# Board_Schamatic07.net
KiCad netlist of a schematic drawn in EAGLE
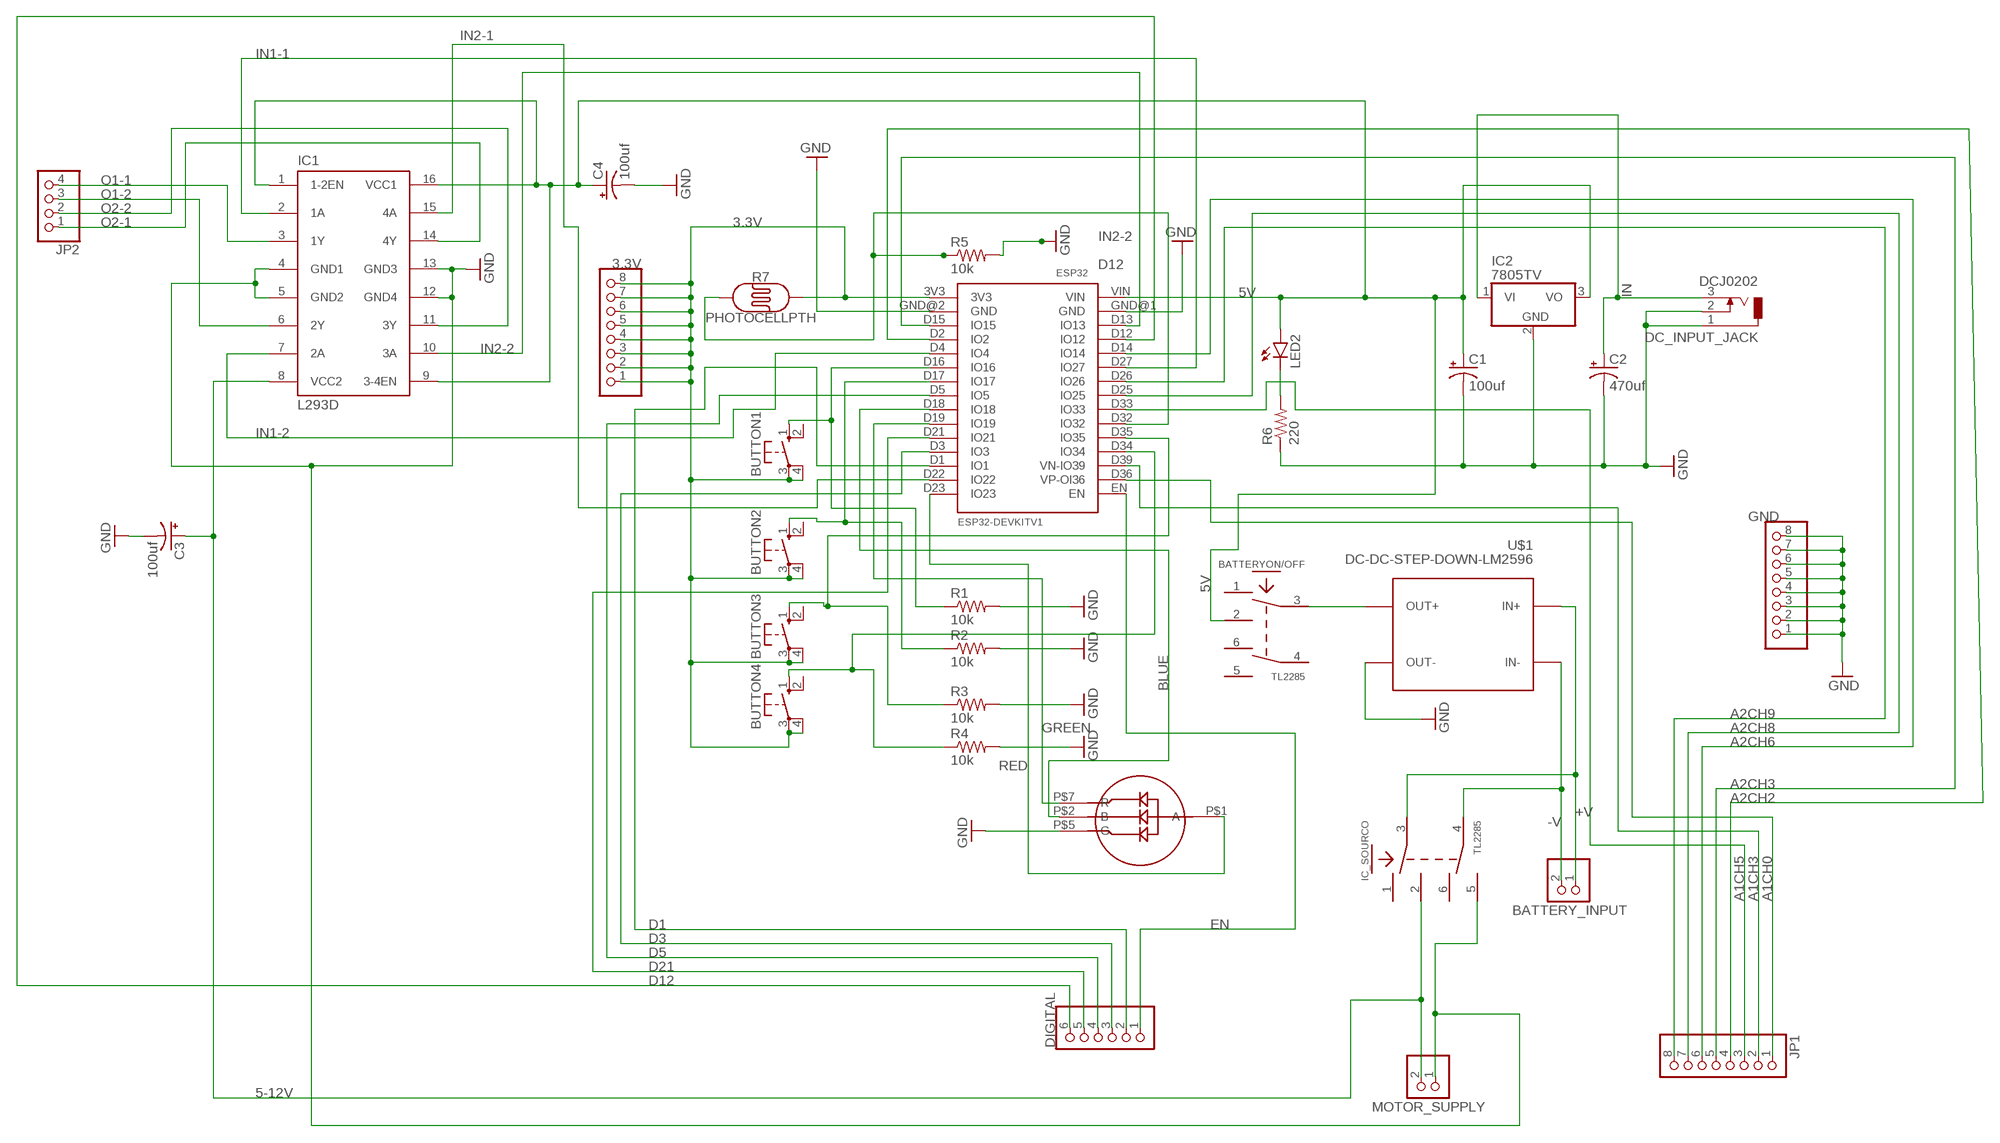
[diagram p0: schematic, sheet 1]

(export (version "E")
  (design (tool "Eeschema 10.0.6"))
  (components
    (comp (ref "3.3V")
      (value "PINHD-1X8")
      (footprint "eagle-import:1X08")
      (libsource (lib "eagle-import") (part "PINHD-1X8"))
    )
    (comp (ref "BATTERYON/OFF")
      (value "TL2285")
      (footprint "eagle-import:TL2285_PCB")
      (libsource (lib "eagle-import") (part "TL2285"))
    )
    (comp (ref "BATTERY_INPUT")
      (value "PINHD-1X2")
      (footprint "eagle-import:1X02")
      (libsource (lib "eagle-import") (part "PINHD-1X2"))
    )
    (comp (ref "BUTTON1")
      (value "10-XX")
      (footprint "eagle-import:B3F-10XX")
      (fields (field (name "MPN") "B3F-1000"))
      (libsource (lib "eagle-import") (part "10-XX"))
    )
    (comp (ref "BUTTON2")
      (value "10-XX")
      (footprint "eagle-import:B3F-10XX")
      (fields (field (name "MPN") "B3F-1000"))
      (libsource (lib "eagle-import") (part "10-XX"))
    )
    (comp (ref "BUTTON3")
      (value "10-XX")
      (footprint "eagle-import:B3F-10XX")
      (fields (field (name "MPN") "B3F-1000"))
      (libsource (lib "eagle-import") (part "10-XX"))
    )
    (comp (ref "BUTTON4")
      (value "10-XX")
      (footprint "eagle-import:B3F-10XX")
      (fields (field (name "MPN") "B3F-1000"))
      (libsource (lib "eagle-import") (part "10-XX"))
    )
    (comp (ref "C1")
      (value "100uf")
      (footprint "eagle-import:E2-5")
      (libsource (lib "eagle-import") (part "CPOL-USE2-5"))
    )
    (comp (ref "C2")
      (value "470uf")
      (footprint "eagle-import:E2-5")
      (libsource (lib "eagle-import") (part "CPOL-USE2-5"))
    )
    (comp (ref "C3")
      (value "100uf")
      (footprint "eagle-import:E2-5")
      (libsource (lib "eagle-import") (part "CPOL-USE2-5"))
    )
    (comp (ref "C4")
      (value "100uf")
      (footprint "eagle-import:E2-5")
      (libsource (lib "eagle-import") (part "CPOL-USE2-5"))
    )
    (comp (ref "DC_INPUT_JACK")
      (value "DCJ0202")
      (footprint "eagle-import:DCJ0202")
      (libsource (lib "eagle-import") (part "DCJ0202"))
    )
    (comp (ref "DIGITAL")
      (value "PINHD-1X6")
      (footprint "eagle-import:1X06")
      (libsource (lib "eagle-import") (part "PINHD-1X6"))
    )
    (comp (ref "ESP32")
      (value "ESP32DEVKITV1")
      (footprint "eagle-import:ESP32-DEVKITV1")
      (libsource (lib "eagle-import") (part "ESP32DEVKITV1"))
    )
    (comp (ref "GND")
      (value "PINHD-1X8")
      (footprint "eagle-import:1X08")
      (libsource (lib "eagle-import") (part "PINHD-1X8"))
    )
    (comp (ref "IC1")
      (value "L293D")
      (footprint "eagle-import:DIL16")
      (libsource (lib "eagle-import") (part "L293D"))
    )
    (comp (ref "IC2")
      (value "7805TV")
      (footprint "eagle-import:TO220V")
      (libsource (lib "eagle-import") (part "78TV05"))
    )
    (comp (ref "IC_SOURCO")
      (value "TL2285")
      (footprint "eagle-import:TL2285_PCB")
      (libsource (lib "eagle-import") (part "TL2285"))
    )
    (comp (ref "JP1")
      (value "PINHD-1X8")
      (footprint "eagle-import:1X08")
      (libsource (lib "eagle-import") (part "PINHD-1X8"))
    )
    (comp (ref "JP2")
      (value "PINHD-1X4")
      (footprint "eagle-import:1X04")
      (libsource (lib "eagle-import") (part "PINHD-1X4"))
    )
    (comp (ref "LED-4_PIN1")
      (value "LED-4_PIN")
      (footprint "eagle-import:LED-4_PIN")
      (libsource (lib "eagle-import") (part "LED-4_PIN"))
    )
    (comp (ref "LED2")
      (value "LED5MM")
      (footprint "eagle-import:LED5MM")
      (libsource (lib "eagle-import") (part "LED5MM"))
    )
    (comp (ref "MOTOR_SUPPLY")
      (value "PINHD-1X2")
      (footprint "eagle-import:1X02")
      (libsource (lib "eagle-import") (part "PINHD-1X2"))
    )
    (comp (ref "R1")
      (value "10k")
      (footprint "eagle-import:0207_10")
      (libsource (lib "eagle-import") (part "R-US_0207/10"))
    )
    (comp (ref "R2")
      (value "10k")
      (footprint "eagle-import:0207_10")
      (libsource (lib "eagle-import") (part "R-US_0207/10"))
    )
    (comp (ref "R3")
      (value "10k")
      (footprint "eagle-import:0207_10")
      (libsource (lib "eagle-import") (part "R-US_0207/10"))
    )
    (comp (ref "R4")
      (value "10k")
      (footprint "eagle-import:0207_10")
      (libsource (lib "eagle-import") (part "R-US_0207/10"))
    )
    (comp (ref "R5")
      (value "10k")
      (footprint "eagle-import:0207_10")
      (libsource (lib "eagle-import") (part "R-US_0207/10"))
    )
    (comp (ref "R6")
      (value "220")
      (footprint "eagle-import:0207_10")
      (libsource (lib "eagle-import") (part "R-US_0207/10"))
    )
    (comp (ref "R7")
      (value "PHOTOCELLPTH")
      (footprint "eagle-import:PHOTOCELL")
      (libsource (lib "eagle-import") (part "PHOTOCELLPTH"))
    )
    (comp (ref "U$1")
      (value "DC-DC-STEP-DOWN-LM2596")
      (footprint "eagle-import:DC-DC-STEP-DOWN-LM2596")
      (libsource (lib "eagle-import") (part "DC-DC-STEP-DOWN-LM2596"))
    )
  )
  (nets
    (net (code "1") (name "/+V") (class "Default")
      (node (ref "BATTERY_INPUT") (pin "1") (pinfunction "1_1") (pintype "passive"))
      (node (ref "IC_SOURCO") (pin "3") (pinfunction "P3_3") (pintype "bidirectional"))
      (node (ref "U$1") (pin "IN+") (pinfunction "IN+_IN+") (pintype "bidirectional"))
    )
    (net (code "2") (name "/-V") (class "Default")
      (node (ref "BATTERY_INPUT") (pin "2") (pinfunction "2_2") (pintype "passive"))
      (node (ref "IC_SOURCO") (pin "4") (pinfunction "P4_4") (pintype "bidirectional"))
      (node (ref "U$1") (pin "IN-") (pinfunction "IN-_IN-") (pintype "bidirectional"))
    )
    (net (code "3") (name "/3.3V") (class "Default")
      (node (ref "3.3V") (pin "1") (pinfunction "1_1") (pintype "passive"))
      (node (ref "3.3V") (pin "2") (pinfunction "2_2") (pintype "passive"))
      (node (ref "3.3V") (pin "3") (pinfunction "3_3") (pintype "passive"))
      (node (ref "3.3V") (pin "4") (pinfunction "4_4") (pintype "passive"))
      (node (ref "3.3V") (pin "5") (pinfunction "5_5") (pintype "passive"))
      (node (ref "3.3V") (pin "6") (pinfunction "6_6") (pintype "passive"))
      (node (ref "3.3V") (pin "7") (pinfunction "7_7") (pintype "passive"))
      (node (ref "3.3V") (pin "8") (pinfunction "8_8") (pintype "passive"))
      (node (ref "BUTTON1") (pin "3") (pinfunction "P_3") (pintype "passive"))
      (node (ref "BUTTON1") (pin "4") (pinfunction "P1_4") (pintype "passive"))
      (node (ref "BUTTON2") (pin "3") (pinfunction "P_3") (pintype "passive"))
      (node (ref "BUTTON2") (pin "4") (pinfunction "P1_4") (pintype "passive"))
      (node (ref "BUTTON3") (pin "3") (pinfunction "P_3") (pintype "passive"))
      (node (ref "BUTTON3") (pin "4") (pinfunction "P1_4") (pintype "passive"))
      (node (ref "BUTTON4") (pin "3") (pinfunction "P_3") (pintype "passive"))
      (node (ref "BUTTON4") (pin "4") (pinfunction "P1_4") (pintype "passive"))
      (node (ref "ESP32") (pin "3V3") (pinfunction "3V3_3V3") (pintype "bidirectional"))
      (node (ref "R7") (pin "2") (pinfunction "P$2_2") (pintype "bidirectional"))
    )
    (net (code "4") (name "/5-12V") (class "Default")
      (node (ref "C3") (pin "+") (pinfunction "+_+") (pintype "passive"))
      (node (ref "IC1") (pin "8") (pinfunction "VCC2_8") (pintype "power_in"))
      (node (ref "IC_SOURCO") (pin "2") (pinfunction "P2_2") (pintype "bidirectional"))
      (node (ref "MOTOR_SUPPLY") (pin "2") (pinfunction "2_2") (pintype "passive"))
    )
    (net (code "5") (name "/5V") (class "Default")
      (node (ref "BATTERYON/OFF") (pin "2") (pinfunction "P2_2") (pintype "bidirectional"))
      (node (ref "C1") (pin "+") (pinfunction "+_+") (pintype "passive"))
      (node (ref "C4") (pin "+") (pinfunction "+_+") (pintype "passive"))
      (node (ref "ESP32") (pin "VIN") (pinfunction "VIN_VIN") (pintype "bidirectional"))
      (node (ref "IC1") (pin "1") (pinfunction "1-2EN_1") (pintype "input"))
      (node (ref "IC1") (pin "16") (pinfunction "VCC1_16") (pintype "power_in"))
      (node (ref "IC1") (pin "9") (pinfunction "3-4EN_9") (pintype "input"))
      (node (ref "IC2") (pin "3") (pinfunction "VO_3") (pintype "passive"))
      (node (ref "LED2") (pin "A") (pinfunction "A_A") (pintype "passive"))
    )
    (net (code "6") (name "/A1CH0") (class "Default")
      (node (ref "ESP32") (pin "D36") (pinfunction "VP-OI36_D36") (pintype "bidirectional"))
      (node (ref "JP1") (pin "1") (pinfunction "1_1") (pintype "passive"))
    )
    (net (code "7") (name "/A1CH3") (class "Default")
      (node (ref "ESP32") (pin "D39") (pinfunction "VN-IO39_D39") (pintype "bidirectional"))
      (node (ref "JP1") (pin "2") (pinfunction "2_2") (pintype "passive"))
    )
    (net (code "8") (name "/A1CH5") (class "Default")
      (node (ref "ESP32") (pin "D33") (pinfunction "IO33_D33") (pintype "bidirectional"))
      (node (ref "JP1") (pin "3") (pinfunction "3_3") (pintype "passive"))
    )
    (net (code "9") (name "/A2CH2") (class "Default")
      (node (ref "ESP32") (pin "D2") (pinfunction "IO2_D2") (pintype "bidirectional"))
      (node (ref "JP1") (pin "4") (pinfunction "4_4") (pintype "passive"))
    )
    (net (code "10") (name "/A2CH3") (class "Default")
      (node (ref "ESP32") (pin "D15") (pinfunction "IO15_D15") (pintype "bidirectional"))
      (node (ref "JP1") (pin "5") (pinfunction "5_5") (pintype "passive"))
    )
    (net (code "11") (name "/A2CH6") (class "Default")
      (node (ref "ESP32") (pin "D14") (pinfunction "IO14_D14") (pintype "bidirectional"))
      (node (ref "JP1") (pin "6") (pinfunction "6_6") (pintype "passive"))
    )
    (net (code "12") (name "/A2CH8") (class "Default")
      (node (ref "ESP32") (pin "D25") (pinfunction "IO25_D25") (pintype "bidirectional"))
      (node (ref "JP1") (pin "7") (pinfunction "7_7") (pintype "passive"))
    )
    (net (code "13") (name "/A2CH9") (class "Default")
      (node (ref "ESP32") (pin "D26") (pinfunction "IO26_D26") (pintype "bidirectional"))
      (node (ref "JP1") (pin "8") (pinfunction "8_8") (pintype "passive"))
    )
    (net (code "14") (name "/BLUE") (class "Default")
      (node (ref "ESP32") (pin "D18") (pinfunction "IO18_D18") (pintype "bidirectional"))
      (node (ref "LED-4_PIN1") (pin "P$2") (pinfunction "B_P$2") (pintype "bidirectional"))
    )
    (net (code "15") (name "/D1") (class "Default")
      (node (ref "DIGITAL") (pin "2") (pinfunction "2_2") (pintype "passive"))
      (node (ref "ESP32") (pin "D1") (pinfunction "IO1_D1") (pintype "bidirectional"))
    )
    (net (code "16") (name "/D3") (class "Default")
      (node (ref "DIGITAL") (pin "3") (pinfunction "3_3") (pintype "passive"))
      (node (ref "ESP32") (pin "D3") (pinfunction "IO3_D3") (pintype "bidirectional"))
    )
    (net (code "17") (name "/D5") (class "Default")
      (node (ref "DIGITAL") (pin "4") (pinfunction "4_4") (pintype "passive"))
      (node (ref "ESP32") (pin "D5") (pinfunction "IO5_D5") (pintype "bidirectional"))
    )
    (net (code "18") (name "/D12") (class "Default")
      (node (ref "DIGITAL") (pin "6") (pinfunction "6_6") (pintype "passive"))
      (node (ref "ESP32") (pin "D12") (pinfunction "IO12_D12") (pintype "bidirectional"))
    )
    (net (code "19") (name "/D21") (class "Default")
      (node (ref "DIGITAL") (pin "5") (pinfunction "5_5") (pintype "passive"))
      (node (ref "ESP32") (pin "D21") (pinfunction "IO21_D21") (pintype "bidirectional"))
    )
    (net (code "20") (name "/EN") (class "Default")
      (node (ref "DIGITAL") (pin "1") (pinfunction "1_1") (pintype "passive"))
      (node (ref "ESP32") (pin "EN") (pinfunction "EN_EN") (pintype "bidirectional"))
    )
    (net (code "21") (name "/GREEN") (class "Default")
      (node (ref "ESP32") (pin "D19") (pinfunction "IO19_D19") (pintype "bidirectional"))
      (node (ref "LED-4_PIN1") (pin "P$7") (pinfunction "R_P$7") (pintype "bidirectional"))
    )
    (net (code "22") (name "/IN") (class "Default")
      (node (ref "C2") (pin "+") (pinfunction "+_+") (pintype "passive"))
      (node (ref "DC_INPUT_JACK") (pin "3") (pinfunction "3_3") (pintype "passive"))
      (node (ref "IC2") (pin "1") (pinfunction "VI_1") (pintype "input"))
    )
    (net (code "23") (name "/IN1-1") (class "Default")
      (node (ref "ESP32") (pin "D27") (pinfunction "IO27_D27") (pintype "bidirectional"))
      (node (ref "IC1") (pin "2") (pinfunction "1A_2") (pintype "input"))
    )
    (net (code "24") (name "/IN1-2") (class "Default")
      (node (ref "ESP32") (pin "D4") (pinfunction "IO4_D4") (pintype "bidirectional"))
      (node (ref "IC1") (pin "7") (pinfunction "2A_7") (pintype "input"))
    )
    (net (code "25") (name "/IN2-1") (class "Default")
      (node (ref "ESP32") (pin "D22") (pinfunction "IO22_D22") (pintype "bidirectional"))
      (node (ref "IC1") (pin "15") (pinfunction "4A_15") (pintype "input"))
    )
    (net (code "26") (name "/IN2-2") (class "Default")
      (node (ref "ESP32") (pin "D13") (pinfunction "IO13_D13") (pintype "bidirectional"))
      (node (ref "IC1") (pin "10") (pinfunction "3A_10") (pintype "input"))
    )
    (net (code "27") (name "/O1-1") (class "Default")
      (node (ref "IC1") (pin "3") (pinfunction "1Y_3") (pintype "output"))
      (node (ref "JP2") (pin "4") (pinfunction "4_4") (pintype "passive"))
    )
    (net (code "28") (name "/O1-2") (class "Default")
      (node (ref "IC1") (pin "6") (pinfunction "2Y_6") (pintype "output"))
      (node (ref "JP2") (pin "3") (pinfunction "3_3") (pintype "passive"))
    )
    (net (code "29") (name "/O2-1") (class "Default")
      (node (ref "IC1") (pin "14") (pinfunction "4Y_14") (pintype "output"))
      (node (ref "JP2") (pin "1") (pinfunction "1_1") (pintype "passive"))
    )
    (net (code "30") (name "/O2-2") (class "Default")
      (node (ref "IC1") (pin "11") (pinfunction "3Y_11") (pintype "output"))
      (node (ref "JP2") (pin "2") (pinfunction "2_2") (pintype "passive"))
    )
    (net (code "31") (name "/RED") (class "Default")
      (node (ref "ESP32") (pin "D23") (pinfunction "IO23_D23") (pintype "bidirectional"))
      (node (ref "LED-4_PIN1") (pin "P$1") (pinfunction "A_P$1") (pintype "bidirectional"))
    )
    (net (code "32") (name "GND") (class "Default")
      (node (ref "C1") (pin "-") (pinfunction "-_-") (pintype "passive"))
      (node (ref "C2") (pin "-") (pinfunction "-_-") (pintype "passive"))
      (node (ref "C3") (pin "-") (pinfunction "-_-") (pintype "passive"))
      (node (ref "C4") (pin "-") (pinfunction "-_-") (pintype "passive"))
      (node (ref "DC_INPUT_JACK") (pin "1") (pinfunction "1_1") (pintype "passive"))
      (node (ref "DC_INPUT_JACK") (pin "2") (pinfunction "2_2") (pintype "passive"))
      (node (ref "ESP32") (pin "GND@1") (pinfunction "GND_GND@1") (pintype "bidirectional"))
      (node (ref "ESP32") (pin "GND@2") (pinfunction "GND_GND@2") (pintype "bidirectional"))
      (node (ref "GND") (pin "1") (pinfunction "1_1") (pintype "passive"))
      (node (ref "GND") (pin "2") (pinfunction "2_2") (pintype "passive"))
      (node (ref "GND") (pin "3") (pinfunction "3_3") (pintype "passive"))
      (node (ref "GND") (pin "4") (pinfunction "4_4") (pintype "passive"))
      (node (ref "GND") (pin "5") (pinfunction "5_5") (pintype "passive"))
      (node (ref "GND") (pin "6") (pinfunction "6_6") (pintype "passive"))
      (node (ref "GND") (pin "7") (pinfunction "7_7") (pintype "passive"))
      (node (ref "GND") (pin "8") (pinfunction "8_8") (pintype "passive"))
      (node (ref "IC1") (pin "12") (pinfunction "GND4_12") (pintype "power_in"))
      (node (ref "IC1") (pin "13") (pinfunction "GND3_13") (pintype "power_in"))
      (node (ref "IC1") (pin "4") (pinfunction "GND1_4") (pintype "power_in"))
      (node (ref "IC1") (pin "5") (pinfunction "GND2_5") (pintype "power_in"))
      (node (ref "IC2") (pin "2") (pinfunction "GND_2") (pintype "passive"))
      (node (ref "IC_SOURCO") (pin "5") (pinfunction "P5_5") (pintype "bidirectional"))
      (node (ref "LED-4_PIN1") (pin "P$5") (pinfunction "G_P$5") (pintype "bidirectional"))
      (node (ref "MOTOR_SUPPLY") (pin "1") (pinfunction "1_1") (pintype "passive"))
      (node (ref "R1") (pin "2") (pinfunction "2_2") (pintype "passive"))
      (node (ref "R2") (pin "2") (pinfunction "2_2") (pintype "passive"))
      (node (ref "R3") (pin "2") (pinfunction "2_2") (pintype "passive"))
      (node (ref "R4") (pin "2") (pinfunction "2_2") (pintype "passive"))
      (node (ref "R5") (pin "2") (pinfunction "2_2") (pintype "passive"))
      (node (ref "R6") (pin "1") (pinfunction "1_1") (pintype "passive"))
      (node (ref "U$1") (pin "OUT-") (pinfunction "OUT-_OUT-") (pintype "bidirectional"))
    )
    (net (code "33") (name "Net-(BATTERYON/OFF-P3)") (class "Default")
      (node (ref "BATTERYON/OFF") (pin "3") (pinfunction "P3_3") (pintype "bidirectional"))
      (node (ref "U$1") (pin "OUT+") (pinfunction "OUT+_OUT+") (pintype "bidirectional"))
    )
    (net (code "34") (name "Net-(BUTTON1-S)") (class "Default")
      (node (ref "BUTTON1") (pin "1") (pinfunction "S_1") (pintype "passive"))
      (node (ref "ESP32") (pin "D16") (pinfunction "IO16_D16") (pintype "bidirectional"))
      (node (ref "R1") (pin "1") (pinfunction "1_1") (pintype "passive"))
    )
    (net (code "35") (name "Net-(BUTTON2-S)") (class "Default")
      (node (ref "BUTTON2") (pin "1") (pinfunction "S_1") (pintype "passive"))
      (node (ref "ESP32") (pin "D17") (pinfunction "IO17_D17") (pintype "bidirectional"))
      (node (ref "R2") (pin "1") (pinfunction "1_1") (pintype "passive"))
    )
    (net (code "36") (name "Net-(BUTTON3-S)") (class "Default")
      (node (ref "BUTTON3") (pin "1") (pinfunction "S_1") (pintype "passive"))
      (node (ref "ESP32") (pin "D35") (pinfunction "IO35_D35") (pintype "bidirectional"))
      (node (ref "R3") (pin "1") (pinfunction "1_1") (pintype "passive"))
    )
    (net (code "37") (name "Net-(BUTTON4-S)") (class "Default")
      (node (ref "BUTTON4") (pin "1") (pinfunction "S_1") (pintype "passive"))
      (node (ref "ESP32") (pin "D34") (pinfunction "IO34_D34") (pintype "bidirectional"))
      (node (ref "R4") (pin "1") (pinfunction "1_1") (pintype "passive"))
    )
    (net (code "38") (name "Net-(ESP32-IO32)") (class "Default")
      (node (ref "ESP32") (pin "D32") (pinfunction "IO32_D32") (pintype "bidirectional"))
      (node (ref "R5") (pin "1") (pinfunction "1_1") (pintype "passive"))
      (node (ref "R7") (pin "1") (pinfunction "P$1_1") (pintype "bidirectional"))
    )
    (net (code "39") (name "Net-(LED2-C)") (class "Default")
      (node (ref "LED2") (pin "K") (pinfunction "C_K") (pintype "passive"))
      (node (ref "R6") (pin "2") (pinfunction "2_2") (pintype "passive"))
    )
    (net (code "40") (name "unconnected-(BATTERYON/OFF-P1-Pad1)") (class "Default")
      (node (ref "BATTERYON/OFF") (pin "1") (pinfunction "P1_1") (pintype "bidirectional"))
    )
    (net (code "41") (name "unconnected-(BATTERYON/OFF-P4-Pad4)") (class "Default")
      (node (ref "BATTERYON/OFF") (pin "4") (pinfunction "P4_4") (pintype "bidirectional"))
    )
    (net (code "42") (name "unconnected-(BATTERYON/OFF-P5-Pad5)") (class "Default")
      (node (ref "BATTERYON/OFF") (pin "5") (pinfunction "P5_5") (pintype "bidirectional"))
    )
    (net (code "43") (name "unconnected-(BATTERYON/OFF-P6-Pad6)") (class "Default")
      (node (ref "BATTERYON/OFF") (pin "6") (pinfunction "P6_6") (pintype "bidirectional"))
    )
    (net (code "44") (name "unconnected-(BUTTON1-S1-Pad2)") (class "Default")
      (node (ref "BUTTON1") (pin "2") (pinfunction "S1_2") (pintype "passive"))
    )
    (net (code "45") (name "unconnected-(BUTTON2-S1-Pad2)") (class "Default")
      (node (ref "BUTTON2") (pin "2") (pinfunction "S1_2") (pintype "passive"))
    )
    (net (code "46") (name "unconnected-(BUTTON3-S1-Pad2)") (class "Default")
      (node (ref "BUTTON3") (pin "2") (pinfunction "S1_2") (pintype "passive"))
    )
    (net (code "47") (name "unconnected-(BUTTON4-S1-Pad2)") (class "Default")
      (node (ref "BUTTON4") (pin "2") (pinfunction "S1_2") (pintype "passive"))
    )
    (net (code "48") (name "unconnected-(IC_SOURCO-P1-Pad1)") (class "Default")
      (node (ref "IC_SOURCO") (pin "1") (pinfunction "P1_1") (pintype "bidirectional"))
    )
    (net (code "49") (name "unconnected-(IC_SOURCO-P6-Pad6)") (class "Default")
      (node (ref "IC_SOURCO") (pin "6") (pinfunction "P6_6") (pintype "bidirectional"))
    )
  )
)
